# Sheet.net
KiCad netlist of a schematic drawn in Altium Designer
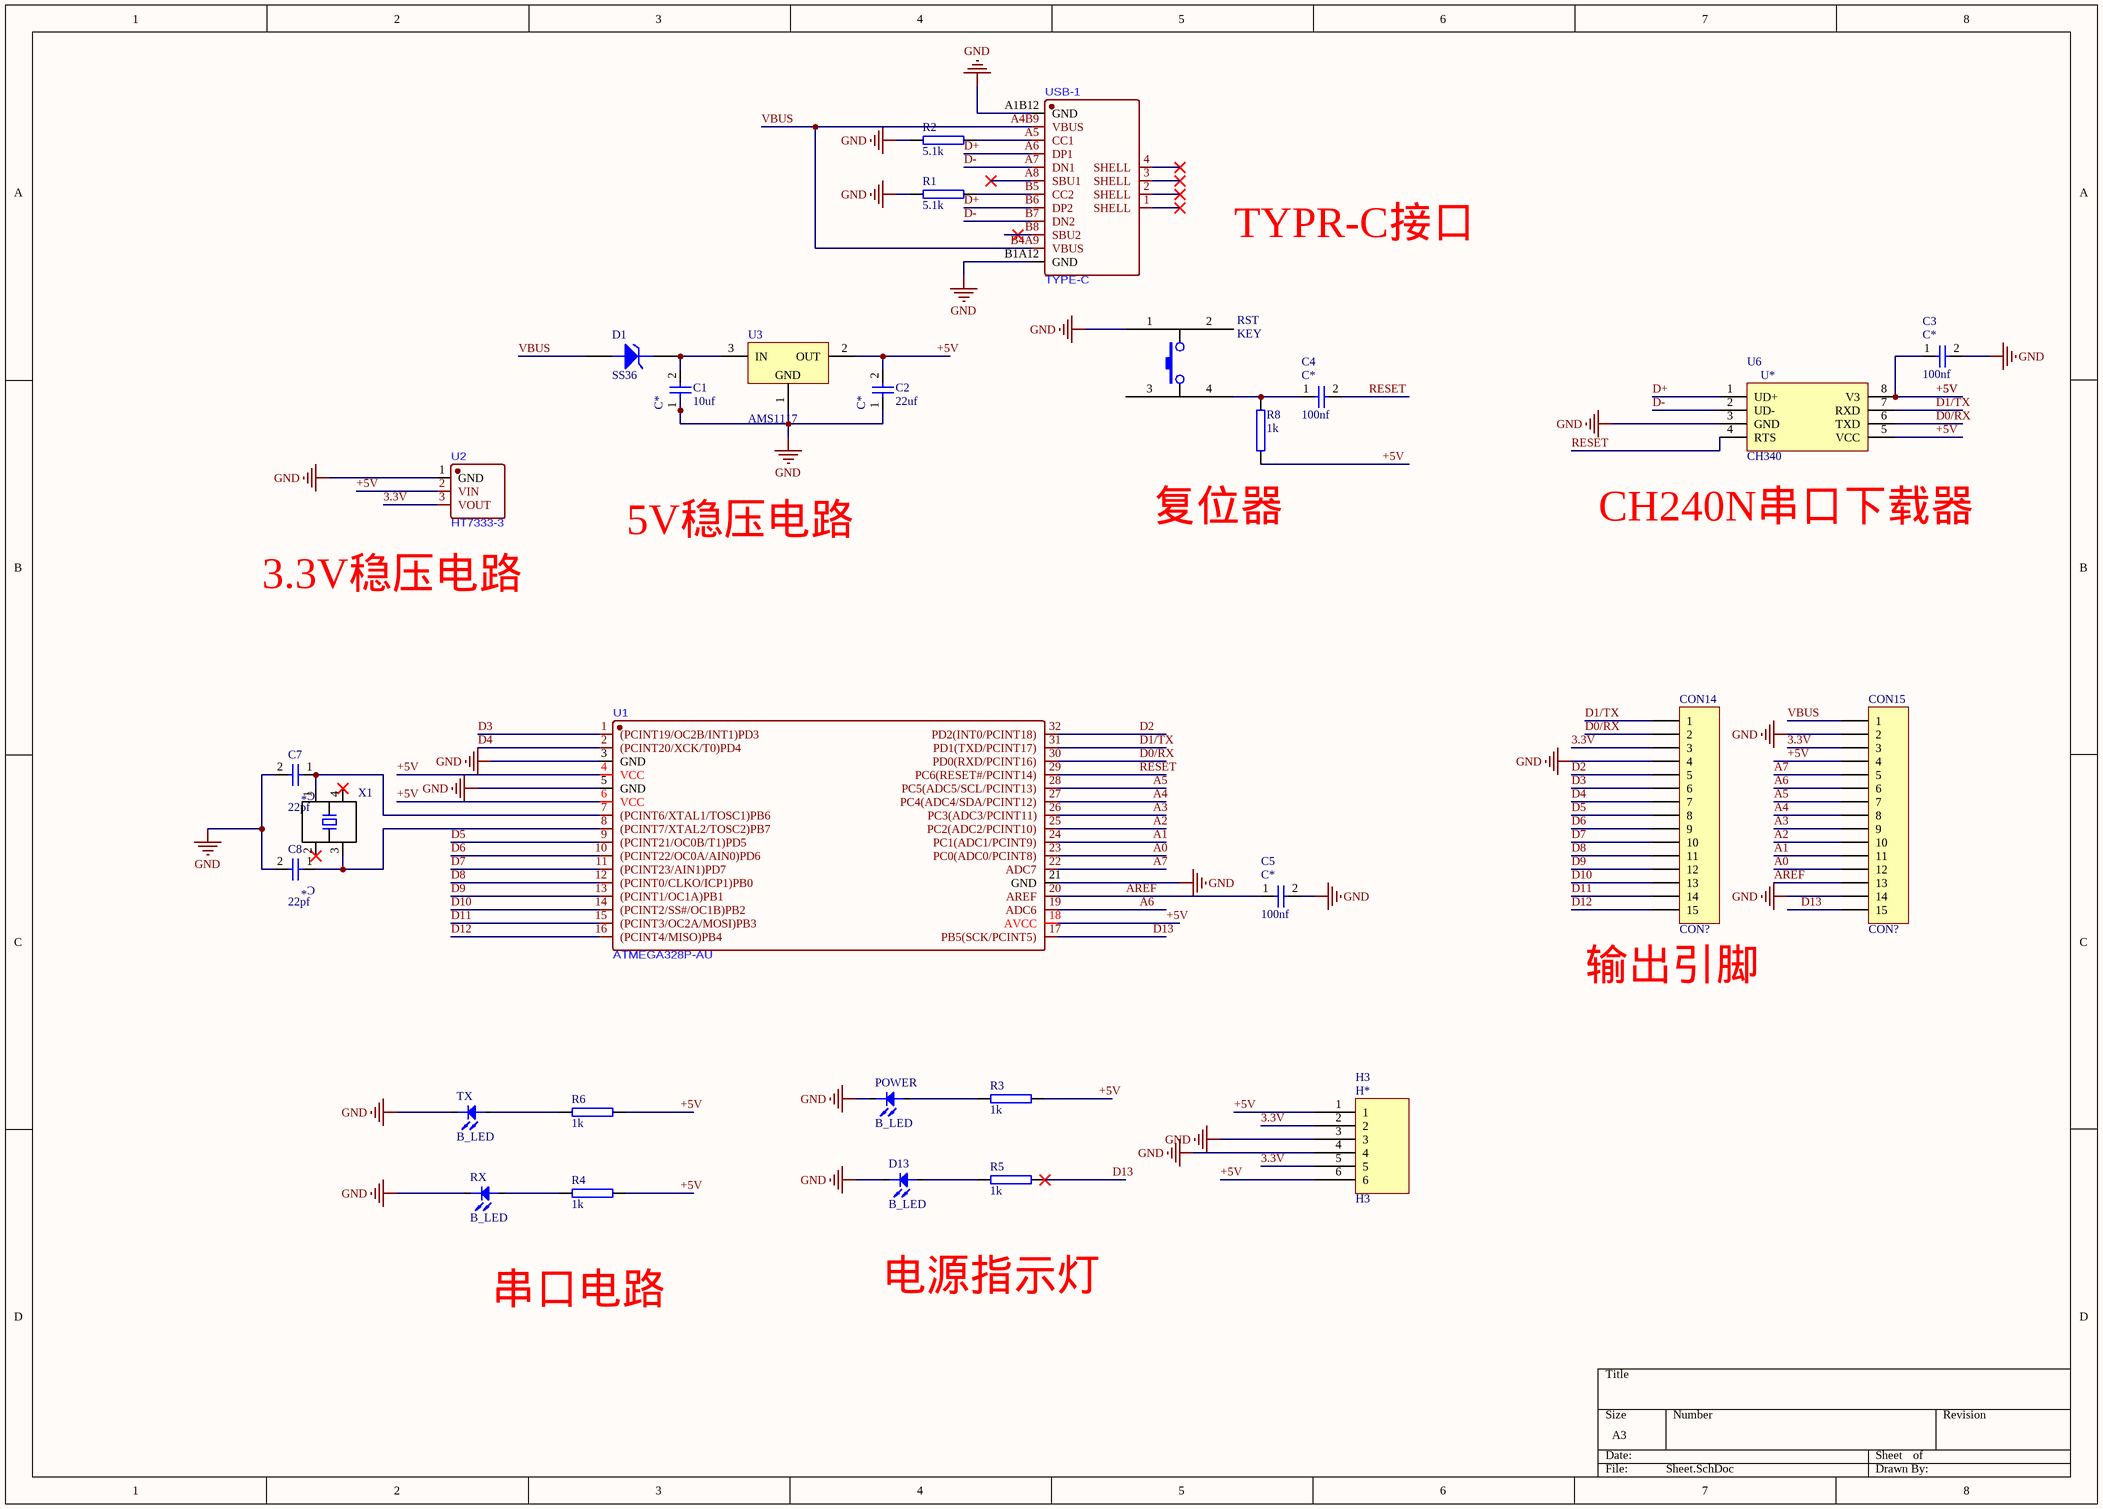
[diagram p0: Sheet.SchDoc]

(export (version "E")
  (design (tool "Eeschema 10.0.6"))
  (components
    (comp (ref "C1")
      (value "10uf")
      (footprint "C0603")
      (description "电容0603")
      (libsource (lib "Schlib") (part "CAP_2"))
    )
    (comp (ref "C2")
      (value "22uf")
      (footprint "C0603")
      (description "电容0603")
      (libsource (lib "Schlib") (part "CAP_3"))
    )
    (comp (ref "C3")
      (value "100nf")
      (footprint "C0603")
      (description "电容0603")
      (libsource (lib "Schlib") (part "CAP_1"))
    )
    (comp (ref "C4")
      (value "100nf")
      (footprint "C0603")
      (description "电容0603")
      (libsource (lib "Schlib") (part "CAP_1"))
    )
    (comp (ref "C5")
      (value "100nf")
      (footprint "C0603")
      (description "电容0603")
      (libsource (lib "Schlib") (part "CAP_1"))
    )
    (comp (ref "C7")
      (value "22pf")
      (footprint "C0603")
      (description "电容0603")
      (libsource (lib "Schlib") (part "CAP"))
    )
    (comp (ref "C8")
      (value "22pf")
      (footprint "C0603")
      (description "电容0603")
      (libsource (lib "Schlib") (part "CAP"))
    )
    (comp (ref "CON14")
      (value "CON?")
      (footprint "HDR-TH_15P-P2.54-V-F - duplicate")
      (description "插针")
      (libsource (lib "Schlib") (part "CON？"))
    )
    (comp (ref "CON15")
      (value "CON?")
      (footprint "HDR-TH_15P-P2.54-V-F")
      (description "插针")
      (libsource (lib "Schlib") (part "CON？"))
    )
    (comp (ref "D1")
      (value "SS36")
      (footprint "SMA_L4.3-W2.6-LS5.2-RD")
      (description "稳压二极管")
      (libsource (lib "Schlib") (part "SS36"))
    )
    (comp (ref "D13")
      (value "B_LED")
      (footprint "LED0603-R-RD")
      (description "LED灯")
      (libsource (lib "Schlib") (part "B_LED"))
    )
    (comp (ref "H3")
      (value "H3")
      (footprint "HDR-TH_6P-P2.54-V_Z-211-0611-0021-001")
      (description "插针")
      (libsource (lib "Schlib") (part "H?"))
    )
    (comp (ref "POWER")
      (value "B_LED")
      (footprint "LED0603-R-RD")
      (description "LED灯")
      (libsource (lib "Schlib") (part "B_LED"))
    )
    (comp (ref "R1")
      (value "5.1k")
      (footprint "R0603")
      (description "电阻")
      (libsource (lib "Schlib") (part "RES_1"))
    )
    (comp (ref "R2")
      (value "5.1k")
      (footprint "R0603")
      (description "电阻")
      (libsource (lib "Schlib") (part "RES_1"))
    )
    (comp (ref "R3")
      (value "1k")
      (footprint "R0603")
      (description "电阻")
      (libsource (lib "Schlib") (part "RES"))
    )
    (comp (ref "R4")
      (value "1k")
      (footprint "R0603")
      (description "电阻")
      (libsource (lib "Schlib") (part "RES"))
    )
    (comp (ref "R5")
      (value "1k")
      (footprint "R0603")
      (description "电阻")
      (libsource (lib "Schlib") (part "RES"))
    )
    (comp (ref "R6")
      (value "1k")
      (footprint "R0603")
      (description "电阻")
      (libsource (lib "Schlib") (part "RES"))
    )
    (comp (ref "R8")
      (value "1k")
      (footprint "R0603")
      (description "电阻")
      (libsource (lib "Schlib") (part "RES"))
    )
    (comp (ref "RST")
      (value "KEY")
      (footprint "KEY-SMD_4P-")
      (description "开关")
      (libsource (lib "Schlib") (part "KEY"))
    )
    (comp (ref "RX")
      (value "B_LED")
      (footprint "LED0603-R-RD")
      (description "LED灯")
      (libsource (lib "Schlib") (part "B_LED"))
    )
    (comp (ref "TX")
      (value "B_LED")
      (footprint "LED0603-R-RD")
      (description "LED灯")
      (libsource (lib "Schlib") (part "B_LED"))
    )
    (comp (ref "U1")
      (value "ATMEGA328P-AU")
      (footprint "arduino--main_IC")
      (description "主芯片")
      (libsource (lib "Schlib") (part "ATMEGA328P-AU"))
    )
    (comp (ref "U2")
      (value "HT7333-3")
      (footprint "SOT-89-3_L4.5-W2.5-P1.50-LS4.2-BR")
      (description "线性稳压芯片")
      (libsource (lib "Schlib") (part "MD8310A"))
    )
    (comp (ref "U3")
      (value "AMS1117")
      (footprint "SOT223_N")
      (description "LDO线性稳压（5v）")
      (libsource (lib "Schlib") (part "AMS1117"))
    )
    (comp (ref "U6") (value "CH340") (footprint "CH340") (libsource (lib "Schlib") (part "CH340")))
    (comp (ref "USB-1")
      (value "TYPE-C")
      (footprint "USB-C-TYPE-C")
      (description "type-c供电插口")
      (libsource (lib "Schlib") (part "TYPE-C"))
    )
    (comp (ref "X1")
      (value "jinzhen")
      (footprint "JINZHEN")
      (description "晶振")
      (libsource (lib "Schlib") (part "JT"))
    )
  )
  (nets
    (net (code "1") (name "/+5V") (class "Default")
      (node (ref "C2") (pin "2") (pinfunction "2_2") (pintype "passive"))
      (node (ref "C3") (pin "1") (pinfunction "1_1") (pintype "passive"))
      (node (ref "CON15") (pin "4") (pinfunction "4_4") (pintype "passive"))
      (node (ref "H3") (pin "1") (pinfunction "1_1") (pintype "passive"))
      (node (ref "H3") (pin "6") (pinfunction "6_6") (pintype "passive"))
      (node (ref "R3") (pin "2") (pinfunction "2_2") (pintype "passive"))
      (node (ref "R4") (pin "2") (pinfunction "2_2") (pintype "passive"))
      (node (ref "R6") (pin "2") (pinfunction "2_2") (pintype "passive"))
      (node (ref "R8") (pin "1") (pinfunction "1_1") (pintype "passive"))
      (node (ref "U1") (pin "18") (pinfunction "AVCC_18") (pintype "passive"))
      (node (ref "U1") (pin "4") (pinfunction "VCC_4") (pintype "passive"))
      (node (ref "U1") (pin "6") (pinfunction "VCC_6") (pintype "passive"))
      (node (ref "U2") (pin "2") (pinfunction "VIN_2") (pintype "passive"))
      (node (ref "U3") (pin "2") (pinfunction "OUT_2") (pintype "passive"))
      (node (ref "U6") (pin "5") (pinfunction "VCC_5") (pintype "passive"))
      (node (ref "U6") (pin "8") (pinfunction "V3_8") (pintype "passive"))
    )
    (net (code "2") (name "/3.3V") (class "Default")
      (node (ref "CON14") (pin "3") (pinfunction "3_3") (pintype "passive"))
      (node (ref "CON15") (pin "3") (pinfunction "3_3") (pintype "passive"))
      (node (ref "H3") (pin "2") (pinfunction "2_2") (pintype "passive"))
      (node (ref "H3") (pin "5") (pinfunction "5_5") (pintype "passive"))
      (node (ref "U2") (pin "3") (pinfunction "VOUT_3") (pintype "passive"))
    )
    (net (code "3") (name "/A0") (class "Default")
      (node (ref "CON15") (pin "12") (pinfunction "12_12") (pintype "passive"))
      (node (ref "U1") (pin "23") (pinfunction "PC0(ADC0/PCINT8)_23") (pintype "passive"))
    )
    (net (code "4") (name "/A1") (class "Default")
      (node (ref "CON15") (pin "11") (pinfunction "11_11") (pintype "passive"))
      (node (ref "U1") (pin "24") (pinfunction "PC1(ADC1/PCINT9)_24") (pintype "passive"))
    )
    (net (code "5") (name "/A2") (class "Default")
      (node (ref "CON15") (pin "10") (pinfunction "10_10") (pintype "passive"))
      (node (ref "U1") (pin "25") (pinfunction "PC2(ADC2/PCINT10)_25") (pintype "passive"))
    )
    (net (code "6") (name "/A3") (class "Default")
      (node (ref "CON15") (pin "9") (pinfunction "9_9") (pintype "passive"))
      (node (ref "U1") (pin "26") (pinfunction "PC3(ADC3/PCINT11)_26") (pintype "passive"))
    )
    (net (code "7") (name "/A4") (class "Default")
      (node (ref "CON15") (pin "8") (pinfunction "8_8") (pintype "passive"))
      (node (ref "U1") (pin "27") (pinfunction "PC4(ADC4/SDA/PCINT12)_27") (pintype "passive"))
    )
    (net (code "8") (name "/A5") (class "Default")
      (node (ref "CON15") (pin "7") (pinfunction "7_7") (pintype "passive"))
      (node (ref "U1") (pin "28") (pinfunction "PC5(ADC5/SCL/PCINT13)_28") (pintype "passive"))
    )
    (net (code "9") (name "/A6") (class "Default")
      (node (ref "CON15") (pin "6") (pinfunction "6_6") (pintype "passive"))
      (node (ref "U1") (pin "19") (pinfunction "ADC6_19") (pintype "passive"))
    )
    (net (code "10") (name "/A7") (class "Default")
      (node (ref "CON15") (pin "5") (pinfunction "5_5") (pintype "passive"))
      (node (ref "U1") (pin "22") (pinfunction "ADC7_22") (pintype "passive"))
    )
    (net (code "11") (name "/AREF") (class "Default")
      (node (ref "C5") (pin "1") (pinfunction "1_1") (pintype "passive"))
      (node (ref "CON15") (pin "13") (pinfunction "13_13") (pintype "passive"))
      (node (ref "U1") (pin "20") (pinfunction "AREF_20") (pintype "passive"))
    )
    (net (code "12") (name "/D+") (class "Default")
      (node (ref "U6") (pin "1") (pinfunction "UD+_1") (pintype "passive"))
      (node (ref "USB-1") (pin "A6") (pinfunction "DP1_A6") (pintype "passive"))
      (node (ref "USB-1") (pin "B6") (pinfunction "DP2_B6") (pintype "passive"))
    )
    (net (code "13") (name "/D-") (class "Default")
      (node (ref "U6") (pin "2") (pinfunction "UD-_2") (pintype "passive"))
      (node (ref "USB-1") (pin "A7") (pinfunction "DN1_A7") (pintype "passive"))
      (node (ref "USB-1") (pin "B7") (pinfunction "DN2_B7") (pintype "passive"))
    )
    (net (code "14") (name "/D0{slash}RX") (class "Default")
      (node (ref "CON14") (pin "2") (pinfunction "2_2") (pintype "passive"))
      (node (ref "U1") (pin "30") (pinfunction "PD0(RXD/PCINT16)_30") (pintype "passive"))
      (node (ref "U6") (pin "6") (pinfunction "TXD_6") (pintype "passive"))
    )
    (net (code "15") (name "/D1{slash}TX") (class "Default")
      (node (ref "CON14") (pin "1") (pinfunction "1_1") (pintype "passive"))
      (node (ref "U1") (pin "31") (pinfunction "PD1(TXD/PCINT17)_31") (pintype "passive"))
      (node (ref "U6") (pin "7") (pinfunction "RXD_7") (pintype "passive"))
    )
    (net (code "16") (name "/D2") (class "Default")
      (node (ref "CON14") (pin "5") (pinfunction "5_5") (pintype "passive"))
      (node (ref "U1") (pin "32") (pinfunction "PD2(INT0/PCINT18)_32") (pintype "passive"))
    )
    (net (code "17") (name "/D3") (class "Default")
      (node (ref "CON14") (pin "6") (pinfunction "6_6") (pintype "passive"))
      (node (ref "U1") (pin "1") (pinfunction "(PCINT19/OC2B/INT1)PD3_1") (pintype "passive"))
    )
    (net (code "18") (name "/D4") (class "Default")
      (node (ref "CON14") (pin "7") (pinfunction "7_7") (pintype "passive"))
      (node (ref "U1") (pin "2") (pinfunction "(PCINT20/XCK/T0)PD4_2") (pintype "passive"))
    )
    (net (code "19") (name "/D5") (class "Default")
      (node (ref "CON14") (pin "8") (pinfunction "8_8") (pintype "passive"))
      (node (ref "U1") (pin "9") (pinfunction "(PCINT21/OC0B/T1)PD5_9") (pintype "passive"))
    )
    (net (code "20") (name "/D6") (class "Default")
      (node (ref "CON14") (pin "9") (pinfunction "9_9") (pintype "passive"))
      (node (ref "U1") (pin "10") (pinfunction "(PCINT22/OC0A/AIN0)PD6_10") (pintype "passive"))
    )
    (net (code "21") (name "/D7") (class "Default")
      (node (ref "CON14") (pin "10") (pinfunction "10_10") (pintype "passive"))
      (node (ref "U1") (pin "11") (pinfunction "(PCINT23/AIN1)PD7_11") (pintype "passive"))
    )
    (net (code "22") (name "/D8") (class "Default")
      (node (ref "CON14") (pin "11") (pinfunction "11_11") (pintype "passive"))
      (node (ref "U1") (pin "12") (pinfunction "(PCINT0/CLKO/ICP1)PB0_12") (pintype "passive"))
    )
    (net (code "23") (name "/D9") (class "Default")
      (node (ref "CON14") (pin "12") (pinfunction "12_12") (pintype "passive"))
      (node (ref "U1") (pin "13") (pinfunction "(PCINT1/OC1A)PB1_13") (pintype "passive"))
    )
    (net (code "24") (name "/D10") (class "Default")
      (node (ref "CON14") (pin "13") (pinfunction "13_13") (pintype "passive"))
      (node (ref "U1") (pin "14") (pinfunction "(PCINT2/SS#/OC1B)PB2_14") (pintype "passive"))
    )
    (net (code "25") (name "/D11") (class "Default")
      (node (ref "CON14") (pin "14") (pinfunction "14_14") (pintype "passive"))
      (node (ref "U1") (pin "15") (pinfunction "(PCINT3/OC2A/MOSI)PB3_15") (pintype "passive"))
    )
    (net (code "26") (name "/D12") (class "Default")
      (node (ref "CON14") (pin "15") (pinfunction "15_15") (pintype "passive"))
      (node (ref "U1") (pin "16") (pinfunction "(PCINT4/MISO)PB4_16") (pintype "passive"))
    )
    (net (code "27") (name "/D13") (class "Default")
      (node (ref "CON15") (pin "15") (pinfunction "15_15") (pintype "passive"))
      (node (ref "R5") (pin "2") (pinfunction "2_2") (pintype "passive"))
      (node (ref "U1") (pin "17") (pinfunction "PB5(SCK/PCINT5)_17") (pintype "passive"))
    )
    (net (code "28") (name "/RESET") (class "Default")
      (node (ref "C4") (pin "2") (pinfunction "2_2") (pintype "passive"))
      (node (ref "U1") (pin "29") (pinfunction "PC6(RESET#/PCINT14)_29") (pintype "passive"))
      (node (ref "U6") (pin "4") (pinfunction "RTS_4") (pintype "passive"))
    )
    (net (code "29") (name "/VBUS") (class "Default")
      (node (ref "CON15") (pin "1") (pinfunction "1_1") (pintype "passive"))
      (node (ref "D1") (pin "1") (pinfunction "A_1") (pintype "passive"))
      (node (ref "USB-1") (pin "A4B9") (pinfunction "VBUS_A4B9") (pintype "passive"))
      (node (ref "USB-1") (pin "B4A9") (pinfunction "VBUS_B4A9") (pintype "passive"))
    )
    (net (code "30") (name "GND") (class "Default")
      (node (ref "C1") (pin "1") (pinfunction "1_1") (pintype "passive"))
      (node (ref "C2") (pin "1") (pinfunction "1_1") (pintype "passive"))
      (node (ref "C3") (pin "2") (pinfunction "2_2") (pintype "passive"))
      (node (ref "C5") (pin "2") (pinfunction "2_2") (pintype "passive"))
      (node (ref "C7") (pin "2") (pinfunction "2_2") (pintype "passive"))
      (node (ref "C8") (pin "2") (pinfunction "2_2") (pintype "passive"))
      (node (ref "CON14") (pin "4") (pinfunction "4_4") (pintype "passive"))
      (node (ref "CON15") (pin "14") (pinfunction "14_14") (pintype "passive"))
      (node (ref "CON15") (pin "2") (pinfunction "2_2") (pintype "passive"))
      (node (ref "D13") (pin "2") (pinfunction "2_2") (pintype "passive"))
      (node (ref "H3") (pin "3") (pinfunction "3_3") (pintype "passive"))
      (node (ref "H3") (pin "4") (pinfunction "4_4") (pintype "passive"))
      (node (ref "POWER") (pin "2") (pinfunction "2_2") (pintype "passive"))
      (node (ref "R1") (pin "1") (pinfunction "1_1") (pintype "passive"))
      (node (ref "R2") (pin "1") (pinfunction "1_1") (pintype "passive"))
      (node (ref "RST") (pin "1") (pinfunction "1_1") (pintype "passive"))
      (node (ref "RX") (pin "2") (pinfunction "2_2") (pintype "passive"))
      (node (ref "TX") (pin "2") (pinfunction "2_2") (pintype "passive"))
      (node (ref "U1") (pin "21") (pinfunction "GND_21") (pintype "passive"))
      (node (ref "U1") (pin "3") (pinfunction "GND_3") (pintype "passive"))
      (node (ref "U1") (pin "5") (pinfunction "GND_5") (pintype "passive"))
      (node (ref "U2") (pin "1") (pinfunction "GND_1") (pintype "passive"))
      (node (ref "U3") (pin "1") (pinfunction "GND_1") (pintype "passive"))
      (node (ref "U6") (pin "3") (pinfunction "GND_3") (pintype "passive"))
      (node (ref "USB-1") (pin "A1B12") (pinfunction "GND_A1B12") (pintype "passive"))
      (node (ref "USB-1") (pin "B1A12") (pinfunction "GND_B1A12") (pintype "passive"))
    )
    (net (code "31") (name "Net-(C4-Pad1)") (class "Default")
      (node (ref "C4") (pin "1") (pinfunction "1_1") (pintype "passive"))
      (node (ref "R8") (pin "2") (pinfunction "2_2") (pintype "passive"))
      (node (ref "RST") (pin "4") (pinfunction "4_4") (pintype "passive"))
    )
    (net (code "32") (name "Net-(D1-K)") (class "Default")
      (node (ref "C1") (pin "2") (pinfunction "2_2") (pintype "passive"))
      (node (ref "D1") (pin "2") (pinfunction "K_2") (pintype "passive"))
      (node (ref "U3") (pin "3") (pinfunction "IN_3") (pintype "passive"))
    )
    (net (code "33") (name "Net-(D13-Pad1)") (class "Default")
      (node (ref "D13") (pin "1") (pinfunction "1_1") (pintype "passive"))
      (node (ref "R5") (pin "1") (pinfunction "1_1") (pintype "passive"))
    )
    (net (code "34") (name "Net-(POWER-Pad1)") (class "Default")
      (node (ref "POWER") (pin "1") (pinfunction "1_1") (pintype "passive"))
      (node (ref "R3") (pin "1") (pinfunction "1_1") (pintype "passive"))
    )
    (net (code "35") (name "Net-(R4-Pad1)") (class "Default")
      (node (ref "R4") (pin "1") (pinfunction "1_1") (pintype "passive"))
      (node (ref "RX") (pin "1") (pinfunction "1_1") (pintype "passive"))
    )
    (net (code "36") (name "Net-(R6-Pad1)") (class "Default")
      (node (ref "R6") (pin "1") (pinfunction "1_1") (pintype "passive"))
      (node (ref "TX") (pin "1") (pinfunction "1_1") (pintype "passive"))
    )
    (net (code "37") (name "Net-(U1-(PCINT6{slash}XTAL1{slash}TOSC1)PB6)") (class "Default")
      (node (ref "C7") (pin "1") (pinfunction "1_1") (pintype "passive"))
      (node (ref "U1") (pin "7") (pinfunction "(PCINT6/XTAL1/TOSC1)PB6_7") (pintype "passive"))
      (node (ref "X1") (pin "1") (pinfunction "1_1") (pintype "passive"))
    )
    (net (code "38") (name "Net-(U1-(PCINT7{slash}XTAL2{slash}TOSC2)PB7)") (class "Default")
      (node (ref "C8") (pin "1") (pinfunction "1_1") (pintype "passive"))
      (node (ref "U1") (pin "8") (pinfunction "(PCINT7/XTAL2/TOSC2)PB7_8") (pintype "passive"))
      (node (ref "X1") (pin "3") (pinfunction "3_3") (pintype "passive"))
    )
    (net (code "39") (name "Net-(USB-1-CC1)") (class "Default")
      (node (ref "R2") (pin "2") (pinfunction "2_2") (pintype "passive"))
      (node (ref "USB-1") (pin "A5") (pinfunction "CC1_A5") (pintype "passive"))
    )
    (net (code "40") (name "Net-(USB-1-CC2)") (class "Default")
      (node (ref "R1") (pin "2") (pinfunction "2_2") (pintype "passive"))
      (node (ref "USB-1") (pin "B5") (pinfunction "CC2_B5") (pintype "passive"))
    )
    (net (code "41") (name "unconnected-(RST-Pad1)") (class "Default")
      (node (ref "RST") (pin "1") (pinfunction "1_1") (pintype "passive"))
    )
    (net (code "42") (name "unconnected-(RST-Pad2)") (class "Default")
      (node (ref "RST") (pin "2") (pinfunction "2_2") (pintype "passive"))
    )
    (net (code "43") (name "unconnected-(RST-Pad2)_1") (class "Default")
      (node (ref "RST") (pin "2") (pinfunction "2_2") (pintype "passive"))
    )
    (net (code "44") (name "unconnected-(RST-Pad3)") (class "Default")
      (node (ref "RST") (pin "3") (pinfunction "3_3") (pintype "passive"))
    )
    (net (code "45") (name "unconnected-(USB-1-SBU1-PadA8)") (class "Default")
      (node (ref "USB-1") (pin "A8") (pinfunction "SBU1_A8") (pintype "passive+no_connect"))
    )
    (net (code "46") (name "unconnected-(USB-1-SBU2-PadB8)") (class "Default")
      (node (ref "USB-1") (pin "B8") (pinfunction "SBU2_B8") (pintype "passive"))
    )
    (net (code "47") (name "unconnected-(USB-1-SHELL-Pad1)") (class "Default")
      (node (ref "USB-1") (pin "1") (pinfunction "SHELL_1") (pintype "passive+no_connect"))
    )
    (net (code "48") (name "unconnected-(USB-1-SHELL-Pad2)") (class "Default")
      (node (ref "USB-1") (pin "2") (pinfunction "SHELL_2") (pintype "passive+no_connect"))
    )
    (net (code "49") (name "unconnected-(USB-1-SHELL-Pad3)") (class "Default")
      (node (ref "USB-1") (pin "3") (pinfunction "SHELL_3") (pintype "passive+no_connect"))
    )
    (net (code "50") (name "unconnected-(USB-1-SHELL-Pad4)") (class "Default")
      (node (ref "USB-1") (pin "4") (pinfunction "SHELL_4") (pintype "passive+no_connect"))
    )
    (net (code "51") (name "unconnected-(X1-Pad1)") (class "Default")
      (node (ref "X1") (pin "1") (pinfunction "1_1") (pintype "passive"))
    )
    (net (code "52") (name "unconnected-(X1-Pad2)") (class "Default")
      (node (ref "X1") (pin "2") (pinfunction "2_2") (pintype "passive+no_connect"))
    )
    (net (code "53") (name "unconnected-(X1-Pad2)") (class "Default")
      (node (ref "X1") (pin "2") (pinfunction "2_2") (pintype "passive"))
    )
    (net (code "54") (name "unconnected-(X1-Pad4)") (class "Default")
      (node (ref "X1") (pin "4") (pinfunction "4_4") (pintype "passive+no_connect"))
    )
  )
)
